# freiBot_pro_micro_SMD_v1_0.net
KiCad netlist of a schematic drawn in EAGLE
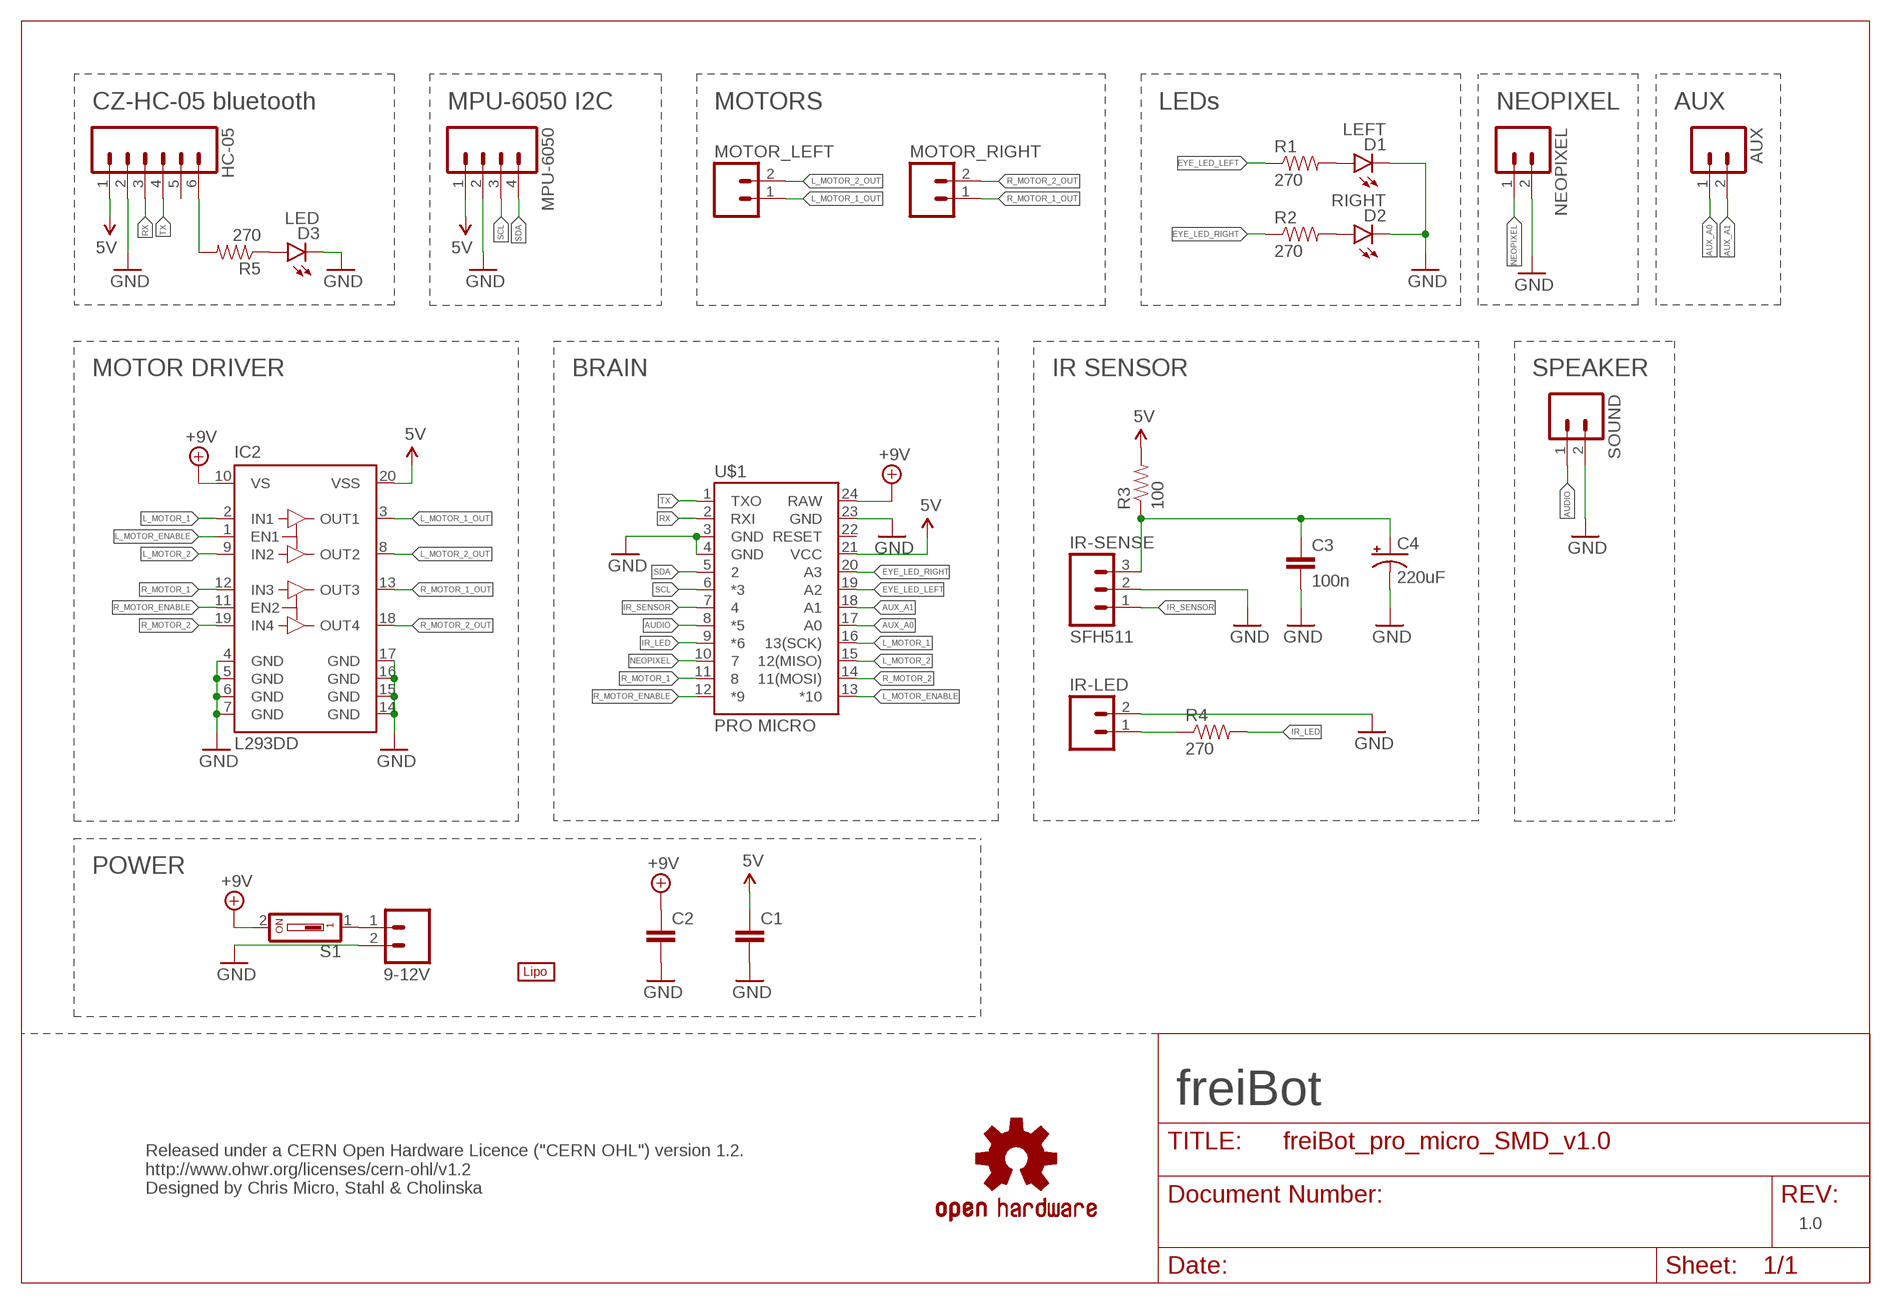
[diagram p0: schematic, sheet 1]

(export (version "E")
  (design (tool "Eeschema 10.0.6"))
  (components
    (comp (ref "9-12V")
      (value "M025MM")
      (footprint "eagle-import:SCREWTERMINAL-5MM-2")
      (libsource (lib "eagle-import") (part "M025MM"))
    )
    (comp (ref "AUX")
      (value "M02LOCK_LONGPADS")
      (footprint "eagle-import:1X02_LOCK_LONGPADS")
      (libsource (lib "eagle-import") (part "M02LOCK_LONGPADS"))
    )
    (comp (ref "C1")
      (value "CAP1206")
      (footprint "eagle-import:1206")
      (libsource (lib "eagle-import") (part "CAP1206"))
    )
    (comp (ref "C2")
      (value "CAP1206")
      (footprint "eagle-import:1206")
      (libsource (lib "eagle-import") (part "CAP1206"))
    )
    (comp (ref "C3")
      (value "100n")
      (footprint "eagle-import:1206")
      (libsource (lib "eagle-import") (part "CAP1206"))
    )
    (comp (ref "C4")
      (value "220uF")
      (footprint "eagle-import:EIA3216")
      (libsource (lib "eagle-import") (part "CAP_POL1206"))
    )
    (comp (ref "D1")
      (value "LEFT")
      (footprint "eagle-import:LED3MM")
      (libsource (lib "eagle-import") (part "LED3MM"))
    )
    (comp (ref "D2")
      (value "RIGHT")
      (footprint "eagle-import:LED3MM")
      (libsource (lib "eagle-import") (part "LED3MM"))
    )
    (comp (ref "D3")
      (value "LED")
      (footprint "eagle-import:LED-1206")
      (libsource (lib "eagle-import") (part "LED1206"))
    )
    (comp (ref "HC-05")
      (value "M06LONGPADS")
      (footprint "eagle-import:1X06_LONGPADS")
      (libsource (lib "eagle-import") (part "M06LONGPADS"))
    )
    (comp (ref "IC2")
      (value "L293DD")
      (footprint "eagle-import:SO20")
      (libsource (lib "eagle-import") (part "L293DD"))
    )
    (comp (ref "IR-LED")
      (value "M02LOCK_LONGPADS")
      (footprint "eagle-import:1X02_LOCK_LONGPADS")
      (libsource (lib "eagle-import") (part "M02LOCK_LONGPADS"))
    )
    (comp (ref "IR-SENSE")
      (value "SFH511")
      (footprint "eagle-import:1X03_LONGPADS")
      (libsource (lib "eagle-import") (part "M03LONGPADS"))
    )
    (comp (ref "LOGO1")
      (value "OSHW-LOGOL-COPPER")
      (footprint "eagle-import:OSHW-LOGO-L_COPPER")
      (libsource (lib "eagle-import") (part "OSHW-LOGOL-COPPER"))
    )
    (comp (ref "MOTOR_LEFT")
      (value "M025MM")
      (footprint "eagle-import:SCREWTERMINAL-5MM-2")
      (libsource (lib "eagle-import") (part "M025MM"))
    )
    (comp (ref "MOTOR_RIGHT")
      (value "M025MM")
      (footprint "eagle-import:SCREWTERMINAL-5MM-2")
      (libsource (lib "eagle-import") (part "M025MM"))
    )
    (comp (ref "MPU-6050")
      (value "M04LONGPADS")
      (footprint "eagle-import:1X04_LONGPADS")
      (libsource (lib "eagle-import") (part "M04LONGPADS"))
    )
    (comp (ref "NEOPIXEL")
      (value "M02LOCK_LONGPADS")
      (footprint "eagle-import:1X02_LOCK_LONGPADS")
      (libsource (lib "eagle-import") (part "M02LOCK_LONGPADS"))
    )
    (comp (ref "R1")
      (value "270")
      (footprint "eagle-import:1206")
      (libsource (lib "eagle-import") (part "RESISTOR1206"))
    )
    (comp (ref "R2")
      (value "270")
      (footprint "eagle-import:1206")
      (libsource (lib "eagle-import") (part "RESISTOR1206"))
    )
    (comp (ref "R3")
      (value "100")
      (footprint "eagle-import:1206")
      (libsource (lib "eagle-import") (part "RESISTOR1206"))
    )
    (comp (ref "R4")
      (value "270")
      (footprint "eagle-import:1206")
      (libsource (lib "eagle-import") (part "RESISTOR1206"))
    )
    (comp (ref "R5")
      (value "270")
      (footprint "eagle-import:1206")
      (libsource (lib "eagle-import") (part "RESISTOR1206"))
    )
    (comp (ref "S1")
      (value "SD4-01")
      (footprint "eagle-import:SD4-01")
      (libsource (lib "eagle-import") (part "SD4-01"))
    )
    (comp (ref "SOUND")
      (value "M02LOCK_LONGPADS")
      (footprint "eagle-import:1X02_LOCK_LONGPADS")
      (libsource (lib "eagle-import") (part "M02LOCK_LONGPADS"))
    )
    (comp (ref "U$1")
      (value "PRO MICRO")
      (footprint "eagle-import:ARDUINO_PRO_MICRO")
      (libsource (lib "eagle-import") (part "ARDUINO_PRO_MICRO"))
    )
    (comp (ref "U$2")
      (value "LIPO-OUTLINE2000")
      (footprint "eagle-import:LIPO-2000")
      (libsource (lib "eagle-import") (part "LIPO-OUTLINE2000"))
    )
  )
  (nets
    (net (code "1") (name "+9V") (class "Default")
      (node (ref "C2") (pin "1") (pinfunction "1_1") (pintype "passive"))
      (node (ref "IC2") (pin "10") (pinfunction "VS_10") (pintype "power_in"))
      (node (ref "S1") (pin "2") (pinfunction "2_2") (pintype "passive"))
      (node (ref "U$1") (pin "24") (pinfunction "RAW_24") (pintype "bidirectional"))
    )
    (net (code "2") (name "5V") (class "Default")
      (node (ref "C1") (pin "1") (pinfunction "1_1") (pintype "passive"))
      (node (ref "HC-05") (pin "1") (pinfunction "1_1") (pintype "passive"))
      (node (ref "IC2") (pin "20") (pinfunction "VSS_20") (pintype "power_in"))
      (node (ref "MPU-6050") (pin "1") (pinfunction "1_1") (pintype "passive"))
      (node (ref "R3") (pin "2") (pinfunction "2_2") (pintype "passive"))
      (node (ref "U$1") (pin "21") (pinfunction "VCC_21") (pintype "bidirectional"))
    )
    (net (code "3") (name "AUDIO") (class "Default")
      (node (ref "SOUND") (pin "1") (pinfunction "1_1") (pintype "passive"))
      (node (ref "U$1") (pin "8") (pinfunction "*5_8") (pintype "bidirectional"))
    )
    (net (code "4") (name "AUX_A0") (class "Default")
      (node (ref "AUX") (pin "1") (pinfunction "1_1") (pintype "passive"))
      (node (ref "U$1") (pin "17") (pinfunction "A0_17") (pintype "bidirectional"))
    )
    (net (code "5") (name "AUX_A1") (class "Default")
      (node (ref "AUX") (pin "2") (pinfunction "2_2") (pintype "passive"))
      (node (ref "U$1") (pin "18") (pinfunction "A1_18") (pintype "bidirectional"))
    )
    (net (code "6") (name "EYE_LED_LEFT") (class "Default")
      (node (ref "R1") (pin "1") (pinfunction "1_1") (pintype "passive"))
      (node (ref "U$1") (pin "19") (pinfunction "A2_19") (pintype "bidirectional"))
    )
    (net (code "7") (name "EYE_LED_RIGHT") (class "Default")
      (node (ref "R2") (pin "1") (pinfunction "1_1") (pintype "passive"))
      (node (ref "U$1") (pin "20") (pinfunction "A3_20") (pintype "bidirectional"))
    )
    (net (code "8") (name "GND") (class "Default")
      (node (ref "9-12V") (pin "2") (pinfunction "2_2") (pintype "passive"))
      (node (ref "C1") (pin "2") (pinfunction "2_2") (pintype "passive"))
      (node (ref "C2") (pin "2") (pinfunction "2_2") (pintype "passive"))
      (node (ref "C3") (pin "2") (pinfunction "2_2") (pintype "passive"))
      (node (ref "C4") (pin "C") (pinfunction "-_C") (pintype "passive"))
      (node (ref "D1") (pin "K") (pinfunction "C_K") (pintype "passive"))
      (node (ref "D2") (pin "K") (pinfunction "C_K") (pintype "passive"))
      (node (ref "D3") (pin "C") (pinfunction "C_C") (pintype "passive"))
      (node (ref "HC-05") (pin "2") (pinfunction "2_2") (pintype "passive"))
      (node (ref "IC2") (pin "14") (pinfunction "GND_14") (pintype "power_in"))
      (node (ref "IC2") (pin "15") (pinfunction "GND_15") (pintype "power_in"))
      (node (ref "IC2") (pin "16") (pinfunction "GND_16") (pintype "power_in"))
      (node (ref "IC2") (pin "17") (pinfunction "GND_17") (pintype "power_in"))
      (node (ref "IC2") (pin "4") (pinfunction "GND_4") (pintype "power_in"))
      (node (ref "IC2") (pin "5") (pinfunction "GND_5") (pintype "power_in"))
      (node (ref "IC2") (pin "6") (pinfunction "GND_6") (pintype "power_in"))
      (node (ref "IC2") (pin "7") (pinfunction "GND_7") (pintype "power_in"))
      (node (ref "IR-LED") (pin "2") (pinfunction "2_2") (pintype "passive"))
      (node (ref "IR-SENSE") (pin "2") (pinfunction "2_2") (pintype "passive"))
      (node (ref "MPU-6050") (pin "2") (pinfunction "2_2") (pintype "passive"))
      (node (ref "NEOPIXEL") (pin "2") (pinfunction "2_2") (pintype "passive"))
      (node (ref "SOUND") (pin "2") (pinfunction "2_2") (pintype "passive"))
      (node (ref "U$1") (pin "23") (pinfunction "GND_23") (pintype "bidirectional"))
      (node (ref "U$1") (pin "3") (pinfunction "GND_3") (pintype "bidirectional"))
      (node (ref "U$1") (pin "4") (pinfunction "GND_4") (pintype "bidirectional"))
    )
    (net (code "9") (name "IR_LED") (class "Default")
      (node (ref "R4") (pin "2") (pinfunction "2_2") (pintype "passive"))
      (node (ref "U$1") (pin "9") (pinfunction "*6_9") (pintype "bidirectional"))
    )
    (net (code "10") (name "IR_SENSOR") (class "Default")
      (node (ref "IR-SENSE") (pin "1") (pinfunction "1_1") (pintype "passive"))
      (node (ref "U$1") (pin "7") (pinfunction "4_7") (pintype "bidirectional"))
    )
    (net (code "11") (name "L_MOTOR_1") (class "Default")
      (node (ref "IC2") (pin "2") (pinfunction "IN1_2") (pintype "input"))
      (node (ref "U$1") (pin "16") (pinfunction "13(SCK)_16") (pintype "bidirectional"))
    )
    (net (code "12") (name "L_MOTOR_1_OUT") (class "Default")
      (node (ref "IC2") (pin "3") (pinfunction "OUT1_3") (pintype "output"))
      (node (ref "MOTOR_LEFT") (pin "1") (pinfunction "1_1") (pintype "passive"))
    )
    (net (code "13") (name "L_MOTOR_2") (class "Default")
      (node (ref "IC2") (pin "9") (pinfunction "IN2_9") (pintype "input"))
      (node (ref "U$1") (pin "15") (pinfunction "12(MISO)_15") (pintype "bidirectional"))
    )
    (net (code "14") (name "L_MOTOR_2_OUT") (class "Default")
      (node (ref "IC2") (pin "8") (pinfunction "OUT2_8") (pintype "output"))
      (node (ref "MOTOR_LEFT") (pin "2") (pinfunction "2_2") (pintype "passive"))
    )
    (net (code "15") (name "L_MOTOR_ENABLE") (class "Default")
      (node (ref "IC2") (pin "1") (pinfunction "EN1_1") (pintype "input"))
      (node (ref "U$1") (pin "13") (pinfunction "*10_13") (pintype "bidirectional"))
    )
    (net (code "16") (name "NEOPIXEL") (class "Default")
      (node (ref "NEOPIXEL") (pin "1") (pinfunction "1_1") (pintype "passive"))
      (node (ref "U$1") (pin "10") (pinfunction "7_10") (pintype "bidirectional"))
    )
    (net (code "17") (name "Net-(9-12V-Pad1)") (class "Default")
      (node (ref "9-12V") (pin "1") (pinfunction "1_1") (pintype "passive"))
      (node (ref "S1") (pin "1") (pinfunction "1_1") (pintype "passive"))
    )
    (net (code "18") (name "Net-(C4-+)") (class "Default")
      (node (ref "C3") (pin "1") (pinfunction "1_1") (pintype "passive"))
      (node (ref "C4") (pin "A") (pinfunction "+_A") (pintype "passive"))
      (node (ref "IR-SENSE") (pin "3") (pinfunction "3_3") (pintype "passive"))
      (node (ref "R3") (pin "1") (pinfunction "1_1") (pintype "passive"))
    )
    (net (code "19") (name "Net-(D1-PadA)") (class "Default")
      (node (ref "D1") (pin "A") (pinfunction "A_A") (pintype "passive"))
      (node (ref "R1") (pin "2") (pinfunction "2_2") (pintype "passive"))
    )
    (net (code "20") (name "Net-(D2-PadA)") (class "Default")
      (node (ref "D2") (pin "A") (pinfunction "A_A") (pintype "passive"))
      (node (ref "R2") (pin "2") (pinfunction "2_2") (pintype "passive"))
    )
    (net (code "21") (name "Net-(D3-PadA)") (class "Default")
      (node (ref "D3") (pin "A") (pinfunction "A_A") (pintype "passive"))
      (node (ref "R5") (pin "1") (pinfunction "1_1") (pintype "passive"))
    )
    (net (code "22") (name "Net-(HC-05-Pad6)") (class "Default")
      (node (ref "HC-05") (pin "6") (pinfunction "6_6") (pintype "passive"))
      (node (ref "R5") (pin "2") (pinfunction "2_2") (pintype "passive"))
    )
    (net (code "23") (name "Net-(IR-LED-Pad1)") (class "Default")
      (node (ref "IR-LED") (pin "1") (pinfunction "1_1") (pintype "passive"))
      (node (ref "R4") (pin "1") (pinfunction "1_1") (pintype "passive"))
    )
    (net (code "24") (name "RX") (class "Default")
      (node (ref "HC-05") (pin "3") (pinfunction "3_3") (pintype "passive"))
      (node (ref "U$1") (pin "2") (pinfunction "RXI_2") (pintype "bidirectional"))
    )
    (net (code "25") (name "R_MOTOR_1") (class "Default")
      (node (ref "IC2") (pin "12") (pinfunction "IN3_12") (pintype "input"))
      (node (ref "U$1") (pin "11") (pinfunction "8_11") (pintype "bidirectional"))
    )
    (net (code "26") (name "R_MOTOR_1_OUT") (class "Default")
      (node (ref "IC2") (pin "13") (pinfunction "OUT3_13") (pintype "output"))
      (node (ref "MOTOR_RIGHT") (pin "1") (pinfunction "1_1") (pintype "passive"))
    )
    (net (code "27") (name "R_MOTOR_2") (class "Default")
      (node (ref "IC2") (pin "19") (pinfunction "IN4_19") (pintype "input"))
      (node (ref "U$1") (pin "14") (pinfunction "11(MOSI)_14") (pintype "bidirectional"))
    )
    (net (code "28") (name "R_MOTOR_2_OUT") (class "Default")
      (node (ref "IC2") (pin "18") (pinfunction "OUT4_18") (pintype "output"))
      (node (ref "MOTOR_RIGHT") (pin "2") (pinfunction "2_2") (pintype "passive"))
    )
    (net (code "29") (name "R_MOTOR_ENABLE") (class "Default")
      (node (ref "IC2") (pin "11") (pinfunction "EN2_11") (pintype "input"))
      (node (ref "U$1") (pin "12") (pinfunction "*9_12") (pintype "bidirectional"))
    )
    (net (code "30") (name "SCL") (class "Default")
      (node (ref "MPU-6050") (pin "3") (pinfunction "3_3") (pintype "passive"))
      (node (ref "U$1") (pin "6") (pinfunction "*3_6") (pintype "bidirectional"))
    )
    (net (code "31") (name "SDA") (class "Default")
      (node (ref "MPU-6050") (pin "4") (pinfunction "4_4") (pintype "passive"))
      (node (ref "U$1") (pin "5") (pinfunction "2_5") (pintype "bidirectional"))
    )
    (net (code "32") (name "TX") (class "Default")
      (node (ref "HC-05") (pin "4") (pinfunction "4_4") (pintype "passive"))
      (node (ref "U$1") (pin "1") (pinfunction "TXO_1") (pintype "bidirectional"))
    )
    (net (code "33") (name "unconnected-(HC-05-Pad5)") (class "Default")
      (node (ref "HC-05") (pin "5") (pinfunction "5_5") (pintype "passive"))
    )
    (net (code "34") (name "unconnected-(U$1-RESET-Pad22)") (class "Default")
      (node (ref "U$1") (pin "22") (pinfunction "RESET_22") (pintype "bidirectional"))
    )
  )
)
